# OSO-SAFE-A1-04.net
KiCad netlist of a schematic drawn in EAGLE
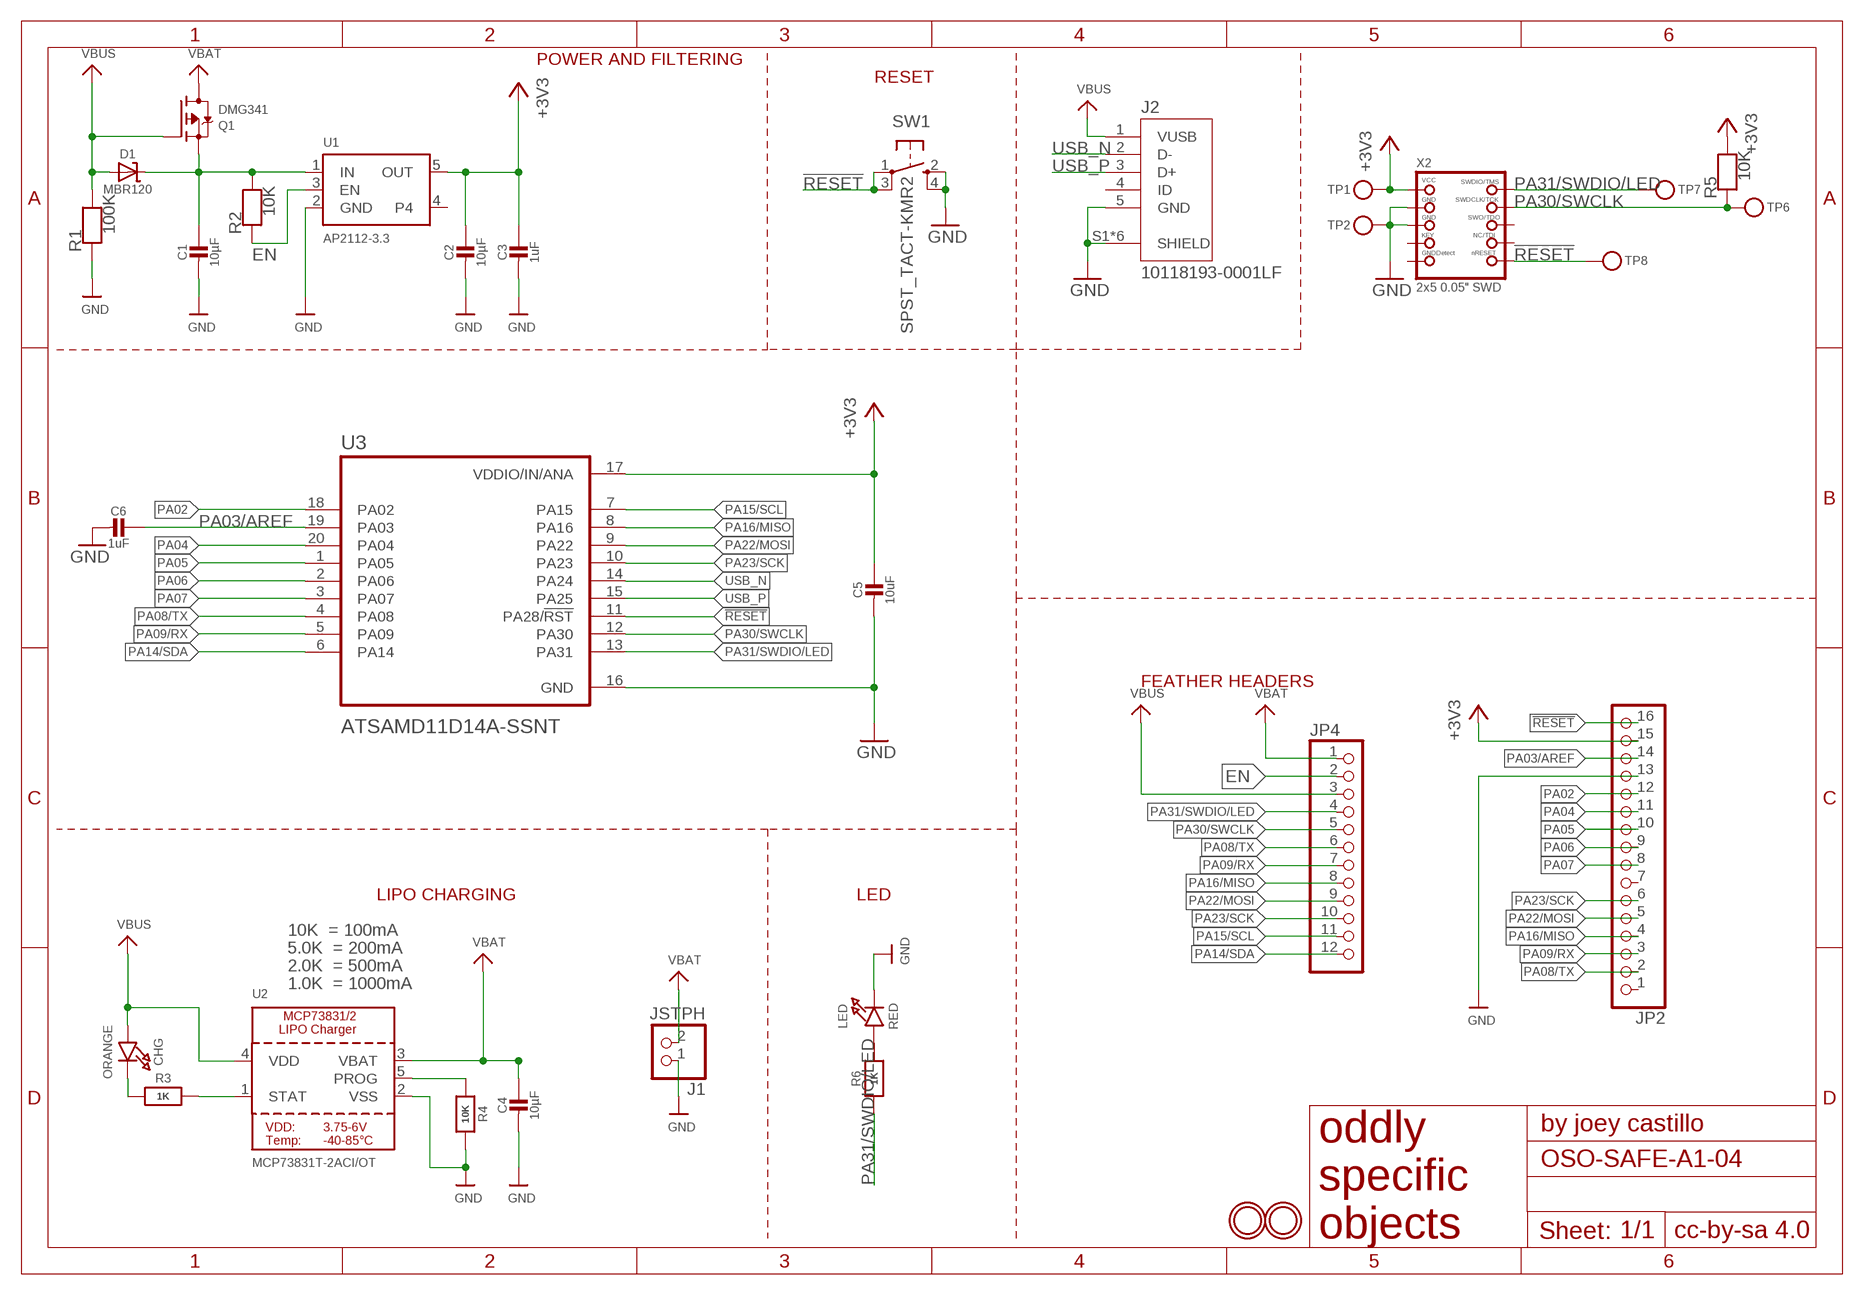
[diagram p0: schematic, sheet 1]

(export (version "E")
  (design (tool "Eeschema 10.0.6"))
  (components
    (comp (ref "C1")
      (value "10µF")
      (footprint "eagle-import:0805-NO")
      (libsource (lib "eagle-import") (part "CAP_CERAMIC0805-NOOUTLINE"))
    )
    (comp (ref "C2")
      (value "10µF")
      (footprint "eagle-import:0805-NO")
      (libsource (lib "eagle-import") (part "CAP_CERAMIC0805-NOOUTLINE"))
    )
    (comp (ref "C3")
      (value "1uF")
      (footprint "eagle-import:0805-NO")
      (libsource (lib "eagle-import") (part "CAP_CERAMIC0805-NOOUTLINE"))
    )
    (comp (ref "C4")
      (value "10µF")
      (footprint "eagle-import:0805-NO")
      (libsource (lib "eagle-import") (part "CAP_CERAMIC0805-NOOUTLINE"))
    )
    (comp (ref "C5")
      (value "10uF")
      (footprint "eagle-import:0805-NO")
      (libsource (lib "eagle-import") (part "CAP_CERAMIC0805-NOOUTLINE"))
    )
    (comp (ref "C6")
      (value "1uF")
      (footprint "eagle-import:0805-NO")
      (libsource (lib "eagle-import") (part "CAP_CERAMIC0805-NOOUTLINE"))
    )
    (comp (ref "CHG")
      (value "ORANGE")
      (footprint "eagle-import:CHIPLED_0805_NOOUTLINE")
      (libsource (lib "eagle-import") (part "LED0805_NOOUTLINE"))
    )
    (comp (ref "D1")
      (value "MBR120")
      (footprint "eagle-import:SOD-123")
      (libsource (lib "eagle-import") (part "DIODE-SCHOTTKYSOD-123"))
    )
    (comp (ref "J1")
      (value "JSTPH")
      (footprint "eagle-import:JSTPH2")
      (libsource (lib "eagle-import") (part "CON_JST_PH_2PIN"))
    )
    (comp (ref "J2")
      (value "10118193-0001LF")
      (footprint "eagle-import:FCI_10118193-0001LF")
      (fields (field (name "DIGI-KEY_PART_NUMBER") "609-4616-1-ND") (field (name "MF") "Amphenol ICC"))
      (libsource (lib "eagle-import") (part "10118193-0001LF"))
    )
    (comp (ref "JP2")
      (value "HEADER-1X16_MIN")
      (footprint "eagle-import:1X16_ROUND_MIN")
      (libsource (lib "eagle-import") (part "HEADER-1X16_MIN"))
    )
    (comp (ref "JP4")
      (value "HEADER-1X12_MIN")
      (footprint "eagle-import:1X12_ROUND_MIN")
      (libsource (lib "eagle-import") (part "HEADER-1X12_MIN"))
    )
    (comp (ref "LED")
      (value "RED")
      (footprint "eagle-import:CHIPLED_0805_NOOUTLINE")
      (libsource (lib "eagle-import") (part "LED0805_NOOUTLINE"))
    )
    (comp (ref "Q1")
      (value "DMG341")
      (footprint "eagle-import:SOT23-R")
      (libsource (lib "eagle-import") (part "MOSFET-P"))
    )
    (comp (ref "R1")
      (value "100K")
      (footprint "eagle-import:0805-NO")
      (libsource (lib "eagle-import") (part "RESISTOR0805_NOOUTLINE"))
    )
    (comp (ref "R2")
      (value "10K")
      (footprint "eagle-import:0805-NO")
      (libsource (lib "eagle-import") (part "RESISTOR0805_NOOUTLINE"))
    )
    (comp (ref "R3")
      (value "1K")
      (footprint "eagle-import:0805-NO")
      (libsource (lib "eagle-import") (part "RESISTOR0805_NOOUTLINE"))
    )
    (comp (ref "R4")
      (value "10K")
      (footprint "eagle-import:0805-NO")
      (libsource (lib "eagle-import") (part "RESISTOR0805_NOOUTLINE"))
    )
    (comp (ref "R5")
      (value "10K")
      (footprint "eagle-import:0805-NO")
      (libsource (lib "eagle-import") (part "RESISTOR0805_NOOUTLINE"))
    )
    (comp (ref "R6")
      (value "1K")
      (footprint "eagle-import:0805-NO")
      (libsource (lib "eagle-import") (part "RESISTOR0805_NOOUTLINE"))
    )
    (comp (ref "SW1")
      (value "SPST_TACT-KMR2")
      (footprint "eagle-import:KMR2")
      (libsource (lib "eagle-import") (part "SPST_TACT-KMR2"))
    )
    (comp (ref "TP1")
      (value "TESTPOINTROUND2MMNO")
      (footprint "eagle-import:TESTPOINT_ROUND_2MM_NO")
      (libsource (lib "eagle-import") (part "TESTPOINTROUND2MMNO"))
    )
    (comp (ref "TP2")
      (value "TESTPOINTROUND2MMNO")
      (footprint "eagle-import:TESTPOINT_ROUND_2MM_NO")
      (libsource (lib "eagle-import") (part "TESTPOINTROUND2MMNO"))
    )
    (comp (ref "TP6")
      (value "TESTPOINTROUND2MMNO")
      (footprint "eagle-import:TESTPOINT_ROUND_2MM_NO")
      (libsource (lib "eagle-import") (part "TESTPOINTROUND2MMNO"))
    )
    (comp (ref "TP7")
      (value "TESTPOINTROUND2MMNO")
      (footprint "eagle-import:TESTPOINT_ROUND_2MM_NO")
      (libsource (lib "eagle-import") (part "TESTPOINTROUND2MMNO"))
    )
    (comp (ref "TP8")
      (value "TESTPOINTROUND2MMNO")
      (footprint "eagle-import:TESTPOINT_ROUND_2MM_NO")
      (libsource (lib "eagle-import") (part "TESTPOINTROUND2MMNO"))
    )
    (comp (ref "U$31")
      (value "MOUNTINGHOLE2.5")
      (footprint "eagle-import:MOUNTINGHOLE_2.5_PLATED")
      (libsource (lib "eagle-import") (part "MOUNTINGHOLE2.5"))
    )
    (comp (ref "U$32")
      (value "MOUNTINGHOLE2.5")
      (footprint "eagle-import:MOUNTINGHOLE_2.5_PLATED")
      (libsource (lib "eagle-import") (part "MOUNTINGHOLE2.5"))
    )
    (comp (ref "U1")
      (value "AP2112-3.3")
      (footprint "eagle-import:SOT23-5")
      (libsource (lib "eagle-import") (part "VREG_SOT23-5"))
    )
    (comp (ref "U2")
      (value "MCP73831T-2ACI/OT")
      (footprint "eagle-import:SOT23-5")
      (libsource (lib "eagle-import") (part "MCP73831/2"))
    )
    (comp (ref "U3")
      (value "ATSAMD11D14A-SSNT")
      (footprint "eagle-import:SOIC127P1030X265-20N")
      (fields (field (name "MF") "Microchip"))
      (libsource (lib "eagle-import") (part "ATSAMD11D14A-SSNT"))
    )
    (comp (ref "X2")
      (value "2x5 0.05\" SWD")
      (footprint "eagle-import:2X05_1.27MM_BOX_NOPOSTS")
      (libsource (lib "eagle-import") (part "JTAG-CORTEXBOX"))
    )
  )
  (nets
    (net (code "1") (name "+3V3") (class "Default")
      (node (ref "C2") (pin "1") (pinfunction "1_1") (pintype "passive"))
      (node (ref "C3") (pin "1") (pinfunction "1_1") (pintype "passive"))
      (node (ref "C5") (pin "1") (pinfunction "1_1") (pintype "passive"))
      (node (ref "JP2") (pin "15") (pinfunction "15_15") (pintype "passive"))
      (node (ref "R5") (pin "2") (pinfunction "2_2") (pintype "passive"))
      (node (ref "TP1") (pin "P$1") (pinfunction "P$1_P$1") (pintype "bidirectional"))
      (node (ref "U1") (pin "5") (pinfunction "OUT_5") (pintype "power_in"))
      (node (ref "U3") (pin "17") (pinfunction "VDDIO/IN/ANA_17") (pintype "power_in"))
      (node (ref "X2") (pin "1") (pinfunction "VCC_1") (pintype "power_in"))
    )
    (net (code "2") (name "/~{RESET}") (class "Default")
      (node (ref "JP2") (pin "16") (pinfunction "16_16") (pintype "passive"))
      (node (ref "SW1") (pin "1") (pinfunction "P_1") (pintype "passive"))
      (node (ref "SW1") (pin "3") (pinfunction "P1_3") (pintype "passive"))
      (node (ref "TP8") (pin "P$1") (pinfunction "P$1_P$1") (pintype "bidirectional"))
      (node (ref "U3") (pin "11") (pinfunction "PA28/~{RST}_11") (pintype "bidirectional"))
      (node (ref "X2") (pin "10") (pinfunction "NRESET_10") (pintype "bidirectional"))
    )
    (net (code "3") (name "EN") (class "Default")
      (node (ref "JP4") (pin "2") (pinfunction "2_2") (pintype "passive"))
      (node (ref "R2") (pin "1") (pinfunction "1_1") (pintype "passive"))
      (node (ref "U1") (pin "3") (pinfunction "EN_3") (pintype "input"))
    )
    (net (code "4") (name "GND") (class "Default")
      (node (ref "C1") (pin "2") (pinfunction "2_2") (pintype "passive"))
      (node (ref "C2") (pin "2") (pinfunction "2_2") (pintype "passive"))
      (node (ref "C3") (pin "2") (pinfunction "2_2") (pintype "passive"))
      (node (ref "C4") (pin "2") (pinfunction "2_2") (pintype "passive"))
      (node (ref "C5") (pin "2") (pinfunction "2_2") (pintype "passive"))
      (node (ref "C6") (pin "2") (pinfunction "2_2") (pintype "passive"))
      (node (ref "J1") (pin "1") (pinfunction "1_1") (pintype "passive"))
      (node (ref "J2") (pin "5") (pinfunction "GND_5") (pintype "passive"))
      (node (ref "J2") (pin "S1") (pinfunction "SHIELD_S1") (pintype "passive"))
      (node (ref "J2") (pin "S2") (pinfunction "SHIELD_S2") (pintype "passive"))
      (node (ref "J2") (pin "S3") (pinfunction "SHIELD_S3") (pintype "passive"))
      (node (ref "J2") (pin "S4") (pinfunction "SHIELD_S4") (pintype "passive"))
      (node (ref "J2") (pin "S5") (pinfunction "SHIELD_S5") (pintype "passive"))
      (node (ref "J2") (pin "S6") (pinfunction "SHIELD_S6") (pintype "passive"))
      (node (ref "JP2") (pin "13") (pinfunction "13_13") (pintype "passive"))
      (node (ref "LED") (pin "C") (pinfunction "C_C") (pintype "passive"))
      (node (ref "R1") (pin "1") (pinfunction "1_1") (pintype "passive"))
      (node (ref "R4") (pin "2") (pinfunction "2_2") (pintype "passive"))
      (node (ref "SW1") (pin "2") (pinfunction "S_2") (pintype "passive"))
      (node (ref "SW1") (pin "4") (pinfunction "S1_4") (pintype "passive"))
      (node (ref "TP2") (pin "P$1") (pinfunction "P$1_P$1") (pintype "bidirectional"))
      (node (ref "U1") (pin "2") (pinfunction "GND_2") (pintype "power_in"))
      (node (ref "U2") (pin "2") (pinfunction "VSS_2") (pintype "power_in"))
      (node (ref "U3") (pin "16") (pinfunction "GND_16") (pintype "power_in"))
      (node (ref "X2") (pin "3") (pinfunction "GND_3") (pintype "power_in"))
      (node (ref "X2") (pin "5") (pinfunction "GND_5") (pintype "power_in"))
    )
    (net (code "5") (name "Net-(CHG-PadC)") (class "Default")
      (node (ref "CHG") (pin "C") (pinfunction "C_C") (pintype "passive"))
      (node (ref "R3") (pin "1") (pinfunction "1_1") (pintype "passive"))
    )
    (net (code "6") (name "Net-(LED-PadA)") (class "Default")
      (node (ref "LED") (pin "A") (pinfunction "A_A") (pintype "passive"))
      (node (ref "R6") (pin "2") (pinfunction "2_2") (pintype "passive"))
    )
    (net (code "7") (name "Net-(Q1-S)") (class "Default")
      (node (ref "C1") (pin "1") (pinfunction "1_1") (pintype "passive"))
      (node (ref "D1") (pin "C") (pinfunction "C_C") (pintype "passive"))
      (node (ref "Q1") (pin "2") (pinfunction "S_2") (pintype "passive"))
      (node (ref "R2") (pin "2") (pinfunction "2_2") (pintype "passive"))
      (node (ref "U1") (pin "1") (pinfunction "IN_1") (pintype "power_in"))
    )
    (net (code "8") (name "Net-(U2-PROG)") (class "Default")
      (node (ref "R4") (pin "1") (pinfunction "1_1") (pintype "passive"))
      (node (ref "U2") (pin "5") (pinfunction "PROG_5") (pintype "input"))
    )
    (net (code "9") (name "Net-(U2-STAT)") (class "Default")
      (node (ref "R3") (pin "2") (pinfunction "2_2") (pintype "passive"))
      (node (ref "U2") (pin "1") (pinfunction "STAT_1") (pintype "output"))
    )
    (net (code "10") (name "PA02") (class "Default")
      (node (ref "JP2") (pin "12") (pinfunction "12_12") (pintype "passive"))
      (node (ref "U3") (pin "18") (pinfunction "PA02_18") (pintype "bidirectional"))
    )
    (net (code "11") (name "PA03{slash}AREF") (class "Default")
      (node (ref "C6") (pin "1") (pinfunction "1_1") (pintype "passive"))
      (node (ref "JP2") (pin "14") (pinfunction "14_14") (pintype "passive"))
      (node (ref "U3") (pin "19") (pinfunction "PA03_19") (pintype "bidirectional"))
    )
    (net (code "12") (name "PA04") (class "Default")
      (node (ref "JP2") (pin "11") (pinfunction "11_11") (pintype "passive"))
      (node (ref "U3") (pin "20") (pinfunction "PA04_20") (pintype "bidirectional"))
    )
    (net (code "13") (name "PA05") (class "Default")
      (node (ref "JP2") (pin "10") (pinfunction "10_10") (pintype "passive"))
      (node (ref "U3") (pin "1") (pinfunction "PA05_1") (pintype "bidirectional"))
    )
    (net (code "14") (name "PA06") (class "Default")
      (node (ref "JP2") (pin "9") (pinfunction "9_9") (pintype "passive"))
      (node (ref "U3") (pin "2") (pinfunction "PA06_2") (pintype "bidirectional"))
    )
    (net (code "15") (name "PA07") (class "Default")
      (node (ref "JP2") (pin "8") (pinfunction "8_8") (pintype "passive"))
      (node (ref "U3") (pin "3") (pinfunction "PA07_3") (pintype "bidirectional"))
    )
    (net (code "16") (name "PA08{slash}TX") (class "Default")
      (node (ref "JP2") (pin "2") (pinfunction "2_2") (pintype "passive"))
      (node (ref "JP4") (pin "6") (pinfunction "6_6") (pintype "passive"))
      (node (ref "U3") (pin "4") (pinfunction "PA08_4") (pintype "bidirectional"))
    )
    (net (code "17") (name "PA09{slash}RX") (class "Default")
      (node (ref "JP2") (pin "3") (pinfunction "3_3") (pintype "passive"))
      (node (ref "JP4") (pin "7") (pinfunction "7_7") (pintype "passive"))
      (node (ref "U3") (pin "5") (pinfunction "PA09_5") (pintype "bidirectional"))
    )
    (net (code "18") (name "PA14{slash}SDA") (class "Default")
      (node (ref "JP4") (pin "12") (pinfunction "12_12") (pintype "passive"))
      (node (ref "U3") (pin "6") (pinfunction "PA14_6") (pintype "bidirectional"))
    )
    (net (code "19") (name "PA15{slash}SCL") (class "Default")
      (node (ref "JP4") (pin "11") (pinfunction "11_11") (pintype "passive"))
      (node (ref "U3") (pin "7") (pinfunction "PA15_7") (pintype "bidirectional"))
    )
    (net (code "20") (name "PA16{slash}MISO") (class "Default")
      (node (ref "JP2") (pin "4") (pinfunction "4_4") (pintype "passive"))
      (node (ref "JP4") (pin "8") (pinfunction "8_8") (pintype "passive"))
      (node (ref "U3") (pin "8") (pinfunction "PA16_8") (pintype "bidirectional"))
    )
    (net (code "21") (name "PA22{slash}MOSI") (class "Default")
      (node (ref "JP2") (pin "5") (pinfunction "5_5") (pintype "passive"))
      (node (ref "JP4") (pin "9") (pinfunction "9_9") (pintype "passive"))
      (node (ref "U3") (pin "9") (pinfunction "PA22_9") (pintype "bidirectional"))
    )
    (net (code "22") (name "PA23{slash}SCK") (class "Default")
      (node (ref "JP2") (pin "6") (pinfunction "6_6") (pintype "passive"))
      (node (ref "JP4") (pin "10") (pinfunction "10_10") (pintype "passive"))
      (node (ref "U3") (pin "10") (pinfunction "PA23_10") (pintype "bidirectional"))
    )
    (net (code "23") (name "PA30{slash}SWCLK") (class "Default")
      (node (ref "JP4") (pin "5") (pinfunction "5_5") (pintype "passive"))
      (node (ref "R5") (pin "1") (pinfunction "1_1") (pintype "passive"))
      (node (ref "TP6") (pin "P$1") (pinfunction "P$1_P$1") (pintype "bidirectional"))
      (node (ref "U3") (pin "12") (pinfunction "PA30_12") (pintype "bidirectional"))
      (node (ref "X2") (pin "4") (pinfunction "SWDCLK_4") (pintype "bidirectional"))
    )
    (net (code "24") (name "PA31{slash}SWDIO{slash}LED") (class "Default")
      (node (ref "JP4") (pin "4") (pinfunction "4_4") (pintype "passive"))
      (node (ref "R6") (pin "1") (pinfunction "1_1") (pintype "passive"))
      (node (ref "TP7") (pin "P$1") (pinfunction "P$1_P$1") (pintype "bidirectional"))
      (node (ref "U3") (pin "13") (pinfunction "PA31_13") (pintype "bidirectional"))
      (node (ref "X2") (pin "2") (pinfunction "SWDIO_2") (pintype "bidirectional"))
    )
    (net (code "25") (name "USB_N") (class "Default")
      (node (ref "J2") (pin "2") (pinfunction "D-_2") (pintype "passive"))
      (node (ref "U3") (pin "14") (pinfunction "PA24_14") (pintype "bidirectional"))
    )
    (net (code "26") (name "USB_P") (class "Default")
      (node (ref "J2") (pin "3") (pinfunction "D+_3") (pintype "passive"))
      (node (ref "U3") (pin "15") (pinfunction "PA25_15") (pintype "bidirectional"))
    )
    (net (code "27") (name "VBAT") (class "Default")
      (node (ref "C4") (pin "1") (pinfunction "1_1") (pintype "passive"))
      (node (ref "J1") (pin "2") (pinfunction "2_2") (pintype "passive"))
      (node (ref "JP4") (pin "1") (pinfunction "1_1") (pintype "passive"))
      (node (ref "Q1") (pin "3") (pinfunction "D_3") (pintype "passive"))
      (node (ref "U2") (pin "3") (pinfunction "VBAT_3") (pintype "power_in"))
    )
    (net (code "28") (name "VBUS") (class "Default")
      (node (ref "CHG") (pin "A") (pinfunction "A_A") (pintype "passive"))
      (node (ref "D1") (pin "A") (pinfunction "A_A") (pintype "passive"))
      (node (ref "J2") (pin "1") (pinfunction "VUSB_1") (pintype "passive"))
      (node (ref "JP4") (pin "3") (pinfunction "3_3") (pintype "passive"))
      (node (ref "Q1") (pin "1") (pinfunction "G_1") (pintype "passive"))
      (node (ref "R1") (pin "2") (pinfunction "2_2") (pintype "passive"))
      (node (ref "U2") (pin "4") (pinfunction "VDD_4") (pintype "power_in"))
    )
    (net (code "29") (name "unconnected-(J2-ID-Pad4)") (class "Default")
      (node (ref "J2") (pin "4") (pinfunction "ID_4") (pintype "passive"))
    )
    (net (code "30") (name "unconnected-(JP2-Pad1)") (class "Default")
      (node (ref "JP2") (pin "1") (pinfunction "1_1") (pintype "passive"))
    )
    (net (code "31") (name "unconnected-(JP2-Pad7)") (class "Default")
      (node (ref "JP2") (pin "7") (pinfunction "7_7") (pintype "passive"))
    )
    (net (code "32") (name "unconnected-(U1-P4-Pad4)") (class "Default")
      (node (ref "U1") (pin "4") (pinfunction "P4_4") (pintype "bidirectional"))
    )
    (net (code "33") (name "unconnected-(X2-GNDDETECT-Pad9)") (class "Default")
      (node (ref "X2") (pin "9") (pinfunction "GNDDETECT_9") (pintype "bidirectional"))
    )
    (net (code "34") (name "unconnected-(X2-KEY-Pad7)") (class "Default")
      (node (ref "X2") (pin "7") (pinfunction "KEY_7") (pintype "bidirectional"))
    )
    (net (code "35") (name "unconnected-(X2-SWO-Pad6)") (class "Default")
      (node (ref "X2") (pin "6") (pinfunction "SWO_6") (pintype "bidirectional"))
    )
    (net (code "36") (name "unconnected-(X2-TDI-Pad8)") (class "Default")
      (node (ref "X2") (pin "8") (pinfunction "TDI_8") (pintype "bidirectional"))
    )
  )
)
